# brainslug_2.net
KiCad netlist of a schematic drawn in EAGLE
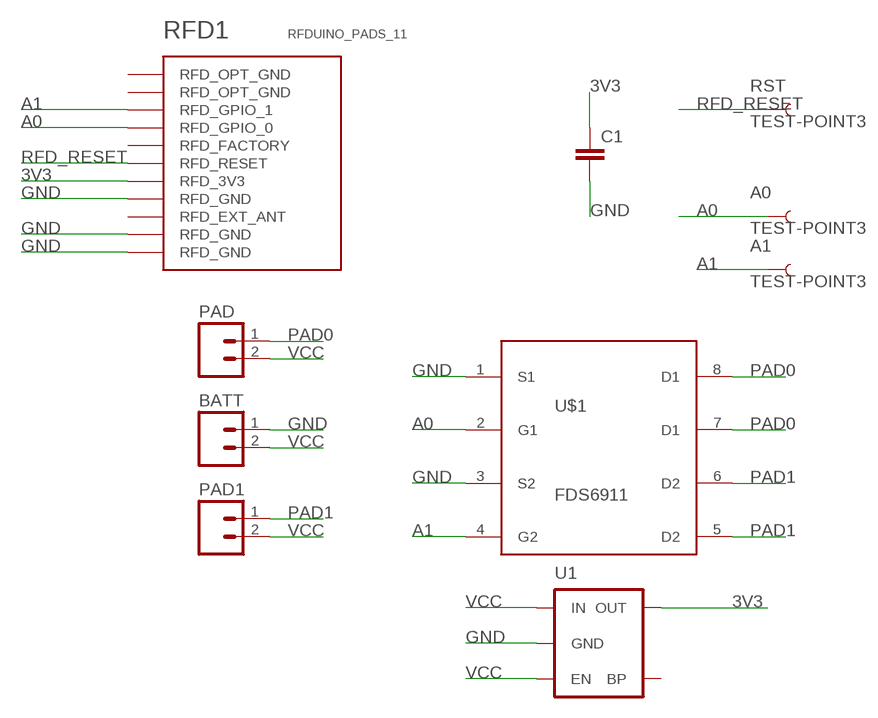
[diagram p0: schematic, sheet 1]

(export (version "E")
  (design (tool "Eeschema 10.0.6"))
  (components
    (comp (ref "A0")
      (value "TEST-POINT3")
      (footprint "eagle-import:PAD.03X.03")
      (libsource (lib "eagle-import") (part "TEST-POINT3"))
    )
    (comp (ref "A1")
      (value "TEST-POINT3")
      (footprint "eagle-import:PAD.03X.03")
      (libsource (lib "eagle-import") (part "TEST-POINT3"))
    )
    (comp (ref "BATT")
      (value "M02-JST-2MM-SMT")
      (footprint "eagle-import:JST-2-SMD")
      (libsource (lib "eagle-import") (part "M02-JST-2MM-SMT"))
    )
    (comp (ref "C1")
      (value "CAP")
      (footprint "eagle-import:C3216")
      (libsource (lib "eagle-import") (part "CAP"))
    )
    (comp (ref "PAD")
      (value "M02-JST-2MM-SMT")
      (footprint "eagle-import:JST-2-SMD")
      (libsource (lib "eagle-import") (part "M02-JST-2MM-SMT"))
    )
    (comp (ref "PAD1")
      (value "M02-JST-2MM-SMT")
      (footprint "eagle-import:JST-2-SMD")
      (libsource (lib "eagle-import") (part "M02-JST-2MM-SMT"))
    )
    (comp (ref "RFD1")
      (value "RFDUINO_PADS_11")
      (footprint "eagle-import:RFDUINO_PADS")
      (libsource (lib "eagle-import") (part "RFDUINO_PADS_11"))
    )
    (comp (ref "RST")
      (value "TEST-POINT3")
      (footprint "eagle-import:PAD.03X.03")
      (libsource (lib "eagle-import") (part "TEST-POINT3"))
    )
    (comp (ref "U$1")
      (value "FDS6911")
      (footprint "eagle-import:SO8")
      (libsource (lib "eagle-import") (part "FDS6911"))
    )
    (comp (ref "U1")
      (value "MIC52053.3V")
      (footprint "eagle-import:SOT23-5")
      (libsource (lib "eagle-import") (part "MIC52053.3V"))
    )
  )
  (nets
    (net (code "1") (name "/3V3") (class "Default")
      (node (ref "C1") (pin "1") (pinfunction "1_1") (pintype "passive"))
      (node (ref "RFD1") (pin "RFD_3V3") (pinfunction "RFD_3V3_RFD_3V3") (pintype "power_in"))
      (node (ref "U1") (pin "5") (pinfunction "OUT_5") (pintype "passive"))
    )
    (net (code "2") (name "/A0") (class "Default")
      (node (ref "A0") (pin "P$1") (pinfunction "1_P$1") (pintype "bidirectional"))
      (node (ref "RFD1") (pin "RFD_GPIO_0") (pinfunction "RFD_GPIO_0_RFD_GPIO_0") (pintype "bidirectional"))
      (node (ref "U$1") (pin "2") (pinfunction "G1_2") (pintype "bidirectional"))
    )
    (net (code "3") (name "/A1") (class "Default")
      (node (ref "A1") (pin "P$1") (pinfunction "1_P$1") (pintype "bidirectional"))
      (node (ref "RFD1") (pin "RFD_GPIO_1") (pinfunction "RFD_GPIO_1_RFD_GPIO_1") (pintype "bidirectional"))
      (node (ref "U$1") (pin "4") (pinfunction "G2_4") (pintype "bidirectional"))
    )
    (net (code "4") (name "/GND") (class "Default")
      (node (ref "BATT") (pin "1") (pinfunction "2_1") (pintype "passive"))
      (node (ref "C1") (pin "2") (pinfunction "2_2") (pintype "passive"))
      (node (ref "RFD1") (pin "RFD_GND@0") (pinfunction "RFD_GND_RFD_GND@0") (pintype "passive"))
      (node (ref "RFD1") (pin "RFD_GND@1") (pinfunction "RFD_GND_RFD_GND@1") (pintype "power_in"))
      (node (ref "RFD1") (pin "RFD_GND@2") (pinfunction "RFD_GND_RFD_GND@2") (pintype "power_in"))
      (node (ref "U$1") (pin "1") (pinfunction "S1_1") (pintype "bidirectional"))
      (node (ref "U$1") (pin "3") (pinfunction "S2_3") (pintype "bidirectional"))
      (node (ref "U1") (pin "2") (pinfunction "GND_2") (pintype "input"))
    )
    (net (code "5") (name "/PAD0") (class "Default")
      (node (ref "PAD") (pin "1") (pinfunction "2_1") (pintype "passive"))
      (node (ref "U$1") (pin "7") (pinfunction "D1_7") (pintype "bidirectional"))
      (node (ref "U$1") (pin "8") (pinfunction "D1_8") (pintype "bidirectional"))
    )
    (net (code "6") (name "/PAD1") (class "Default")
      (node (ref "PAD1") (pin "1") (pinfunction "2_1") (pintype "passive"))
      (node (ref "U$1") (pin "5") (pinfunction "D2_5") (pintype "bidirectional"))
      (node (ref "U$1") (pin "6") (pinfunction "D2_6") (pintype "bidirectional"))
    )
    (net (code "7") (name "/RFD_RESET") (class "Default")
      (node (ref "RFD1") (pin "RFD_RESET") (pinfunction "RFD_RESET_RFD_RESET") (pintype "input"))
      (node (ref "RST") (pin "P$1") (pinfunction "1_P$1") (pintype "bidirectional"))
    )
    (net (code "8") (name "/VCC") (class "Default")
      (node (ref "BATT") (pin "2") (pinfunction "1_2") (pintype "passive"))
      (node (ref "PAD") (pin "2") (pinfunction "1_2") (pintype "passive"))
      (node (ref "PAD1") (pin "2") (pinfunction "1_2") (pintype "passive"))
      (node (ref "U1") (pin "1") (pinfunction "IN_1") (pintype "input"))
      (node (ref "U1") (pin "3") (pinfunction "EN_3") (pintype "input"))
    )
    (net (code "9") (name "unconnected-(RFD1-PadRFD_EXT_ANT)") (class "Default")
      (node (ref "RFD1") (pin "RFD_EXT_ANT") (pinfunction "RFD_EXT_ANT_RFD_EXT_ANT") (pintype "no_connect"))
    )
    (net (code "10") (name "unconnected-(RFD1-PadRFD_FACTORY)") (class "Default")
      (node (ref "RFD1") (pin "RFD_FACTORY") (pinfunction "RFD_FACTORY_RFD_FACTORY") (pintype "no_connect"))
    )
    (net (code "11") (name "unconnected-(RFD1-RFD_OPT_GND-PadRFD_OPT_GND@0)") (class "Default")
      (node (ref "RFD1") (pin "RFD_OPT_GND@0") (pinfunction "RFD_OPT_GND_RFD_OPT_GND@0") (pintype "no_connect"))
    )
    (net (code "12") (name "unconnected-(RFD1-RFD_OPT_GND-PadRFD_OPT_GND@1)") (class "Default")
      (node (ref "RFD1") (pin "RFD_OPT_GND@1") (pinfunction "RFD_OPT_GND_RFD_OPT_GND@1") (pintype "no_connect"))
    )
    (net (code "13") (name "unconnected-(U1-BP-Pad4)") (class "Default")
      (node (ref "U1") (pin "4") (pinfunction "BP_4") (pintype "input"))
    )
  )
)
